# Schematic.net
KiCad netlist of a schematic drawn in EAGLE
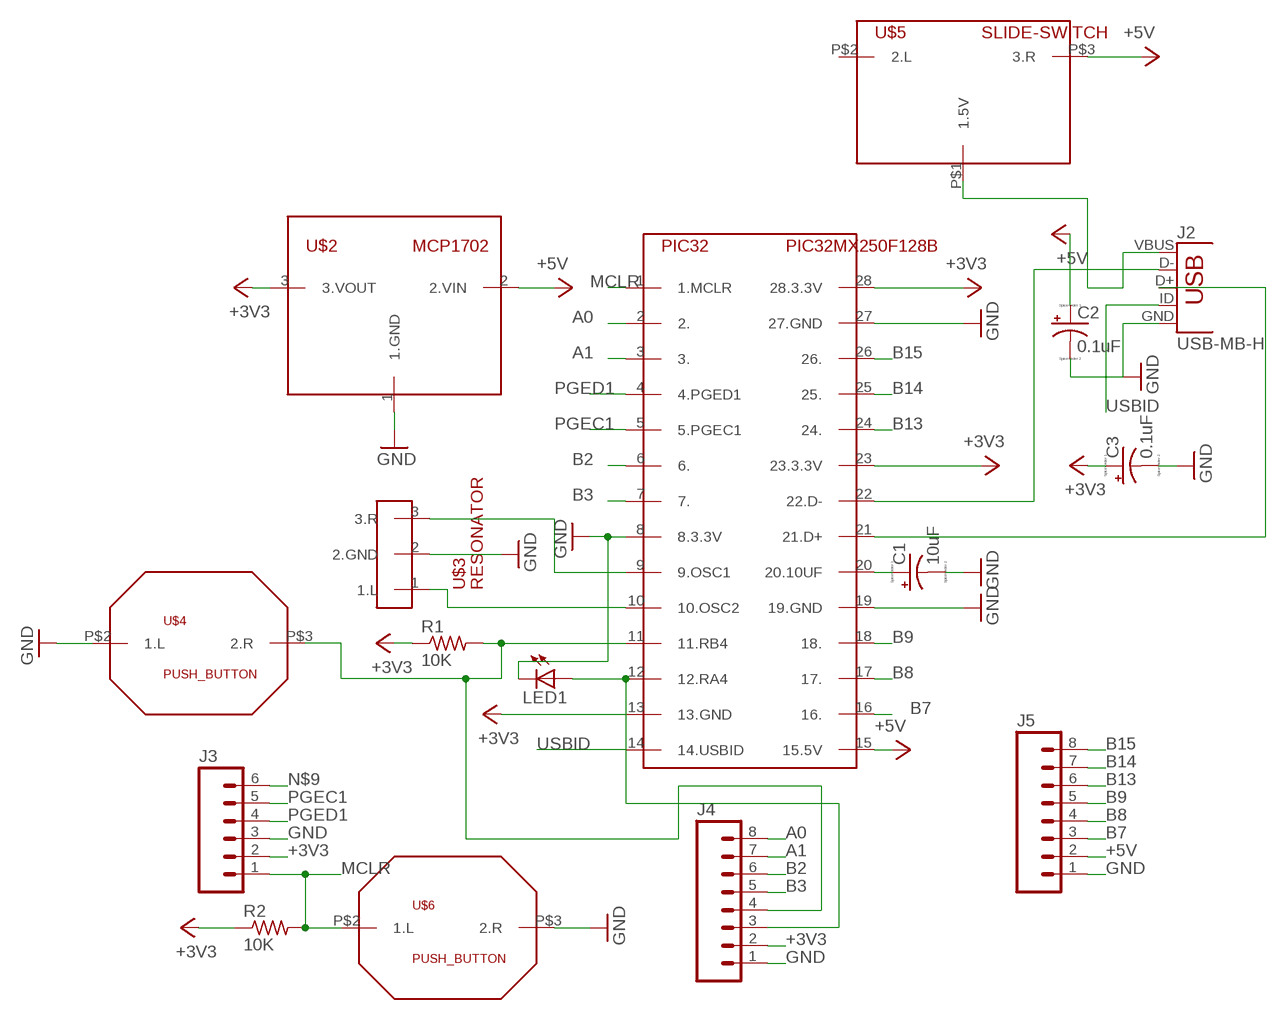
[diagram p0: schematic, sheet 1]

(export (version "E")
  (design (tool "Eeschema 10.0.6"))
  (components
    (comp (ref "C1")
      (value "10uF")
      (footprint "eagle-import:E2,5-5")
      (libsource (lib "eagle-import") (part "CPOL-USE2.5-5"))
    )
    (comp (ref "C2")
      (value "0.1uF")
      (footprint "eagle-import:E2,5-5")
      (libsource (lib "eagle-import") (part "CPOL-USE2.5-5"))
    )
    (comp (ref "C3")
      (value "0.1uF")
      (footprint "eagle-import:E2,5-5")
      (libsource (lib "eagle-import") (part "CPOL-USE2.5-5"))
    )
    (comp (ref "J2")
      (value "USB-MB-H")
      (footprint "eagle-import:USB-MB-H")
      (libsource (lib "eagle-import") (part "USB-MB-H"))
    )
    (comp (ref "J3")
      (value "M06SILK_FEMALE_PTH")
      (footprint "eagle-import:1X06")
      (libsource (lib "eagle-import") (part "M06SILK_FEMALE_PTH"))
    )
    (comp (ref "J4")
      (value "M08SILK_FEMALE_PTH")
      (footprint "eagle-import:1X08")
      (libsource (lib "eagle-import") (part "M08SILK_FEMALE_PTH"))
    )
    (comp (ref "J5")
      (value "M08SILK_FEMALE_PTH")
      (footprint "eagle-import:1X08")
      (libsource (lib "eagle-import") (part "M08SILK_FEMALE_PTH"))
    )
    (comp (ref "LED1")
      (value "LED3MM")
      (footprint "eagle-import:LED3MM")
      (libsource (lib "eagle-import") (part "LED3MM"))
    )
    (comp (ref "PIC32")
      (value "PIC32MX250F128B")
      (footprint "eagle-import:DIL28-3")
      (libsource (lib "eagle-import") (part "PIC32MX250F128B"))
    )
    (comp (ref "R1")
      (value "10K")
      (footprint "eagle-import:0207_10")
      (libsource (lib "eagle-import") (part "R-US_0207/10"))
    )
    (comp (ref "R2")
      (value "10K")
      (footprint "eagle-import:0207_10")
      (libsource (lib "eagle-import") (part "R-US_0207/10"))
    )
    (comp (ref "U$2")
      (value "MCP1702")
      (footprint "eagle-import:TO92")
      (libsource (lib "eagle-import") (part "MCP1702"))
    )
    (comp (ref "U$3")
      (value "RESONATOR")
      (footprint "eagle-import:1X03")
      (libsource (lib "eagle-import") (part "RESONATOR"))
    )
    (comp (ref "U$4")
      (value "PUSH_BUTTON")
      (footprint "eagle-import:PUSH_BUTTON")
      (libsource (lib "eagle-import") (part "PUSH_BUTTON"))
    )
    (comp (ref "U$5")
      (value "SLIDE-SWITCH")
      (footprint "eagle-import:SLIDE-SWITCH")
      (libsource (lib "eagle-import") (part "SLIDE-SWITCH"))
    )
    (comp (ref "U$6")
      (value "PUSH_BUTTON")
      (footprint "eagle-import:PUSH_BUTTON")
      (libsource (lib "eagle-import") (part "PUSH_BUTTON"))
    )
  )
  (nets
    (net (code "1") (name "+3V3") (class "Default")
      (node (ref "C3") (pin "+") (pinfunction "+_+") (pintype "passive"))
      (node (ref "J3") (pin "2") (pinfunction "2_2") (pintype "passive"))
      (node (ref "J4") (pin "2") (pinfunction "2_2") (pintype "passive"))
      (node (ref "PIC32") (pin "13") (pinfunction "13.GND_13") (pintype "bidirectional"))
      (node (ref "PIC32") (pin "23") (pinfunction "23.3.3V_23") (pintype "bidirectional"))
      (node (ref "PIC32") (pin "28") (pinfunction "28.3.3V_28") (pintype "bidirectional"))
      (node (ref "R1") (pin "1") (pinfunction "1_1") (pintype "passive"))
      (node (ref "R2") (pin "1") (pinfunction "1_1") (pintype "passive"))
      (node (ref "U$2") (pin "3") (pinfunction "3.VOUT_3") (pintype "bidirectional"))
    )
    (net (code "2") (name "+5V") (class "Default")
      (node (ref "C2") (pin "+") (pinfunction "+_+") (pintype "passive"))
      (node (ref "J5") (pin "2") (pinfunction "2_2") (pintype "passive"))
      (node (ref "PIC32") (pin "15") (pinfunction "15.5V_15") (pintype "bidirectional"))
      (node (ref "U$2") (pin "2") (pinfunction "2.VIN_2") (pintype "bidirectional"))
      (node (ref "U$5") (pin "P$3") (pinfunction "3.R_P$3") (pintype "bidirectional"))
    )
    (net (code "3") (name "/A0") (class "Default")
      (node (ref "J4") (pin "8") (pinfunction "8_8") (pintype "passive"))
      (node (ref "PIC32") (pin "2") (pinfunction "2._2") (pintype "bidirectional"))
    )
    (net (code "4") (name "/A1") (class "Default")
      (node (ref "J4") (pin "7") (pinfunction "7_7") (pintype "passive"))
      (node (ref "PIC32") (pin "3") (pinfunction "3._3") (pintype "bidirectional"))
    )
    (net (code "5") (name "/B2") (class "Default")
      (node (ref "J4") (pin "6") (pinfunction "6_6") (pintype "passive"))
      (node (ref "PIC32") (pin "6") (pinfunction "6._6") (pintype "bidirectional"))
    )
    (net (code "6") (name "/B3") (class "Default")
      (node (ref "J4") (pin "5") (pinfunction "5_5") (pintype "passive"))
      (node (ref "PIC32") (pin "7") (pinfunction "7._7") (pintype "bidirectional"))
    )
    (net (code "7") (name "/B7") (class "Default")
      (node (ref "J5") (pin "3") (pinfunction "3_3") (pintype "passive"))
      (node (ref "PIC32") (pin "16") (pinfunction "16._16") (pintype "bidirectional"))
    )
    (net (code "8") (name "/B8") (class "Default")
      (node (ref "J5") (pin "4") (pinfunction "4_4") (pintype "passive"))
      (node (ref "PIC32") (pin "17") (pinfunction "17._17") (pintype "bidirectional"))
    )
    (net (code "9") (name "/B9") (class "Default")
      (node (ref "J5") (pin "5") (pinfunction "5_5") (pintype "passive"))
      (node (ref "PIC32") (pin "18") (pinfunction "18._18") (pintype "bidirectional"))
    )
    (net (code "10") (name "/B13") (class "Default")
      (node (ref "J5") (pin "6") (pinfunction "6_6") (pintype "passive"))
      (node (ref "PIC32") (pin "24") (pinfunction "24._24") (pintype "bidirectional"))
    )
    (net (code "11") (name "/B14") (class "Default")
      (node (ref "J5") (pin "7") (pinfunction "7_7") (pintype "passive"))
      (node (ref "PIC32") (pin "25") (pinfunction "25._25") (pintype "bidirectional"))
    )
    (net (code "12") (name "/B15") (class "Default")
      (node (ref "J5") (pin "8") (pinfunction "8_8") (pintype "passive"))
      (node (ref "PIC32") (pin "26") (pinfunction "26._26") (pintype "bidirectional"))
    )
    (net (code "13") (name "/MCLR") (class "Default")
      (node (ref "J3") (pin "1") (pinfunction "1_1") (pintype "passive"))
      (node (ref "PIC32") (pin "1") (pinfunction "1.MCLR_1") (pintype "bidirectional"))
      (node (ref "R2") (pin "2") (pinfunction "2_2") (pintype "passive"))
      (node (ref "U$6") (pin "P$2") (pinfunction "1.L_P$2") (pintype "bidirectional"))
    )
    (net (code "14") (name "/N$9") (class "Default")
      (node (ref "J3") (pin "6") (pinfunction "6_6") (pintype "passive"))
    )
    (net (code "15") (name "/PGEC1") (class "Default")
      (node (ref "J3") (pin "5") (pinfunction "5_5") (pintype "passive"))
      (node (ref "PIC32") (pin "5") (pinfunction "5.PGEC1_5") (pintype "bidirectional"))
    )
    (net (code "16") (name "/PGED1") (class "Default")
      (node (ref "J3") (pin "4") (pinfunction "4_4") (pintype "passive"))
      (node (ref "PIC32") (pin "4") (pinfunction "4.PGED1_4") (pintype "bidirectional"))
    )
    (net (code "17") (name "/USBID") (class "Default")
      (node (ref "J2") (pin "ID") (pinfunction "2.ID_ID") (pintype "bidirectional"))
      (node (ref "PIC32") (pin "14") (pinfunction "14.USBID_14") (pintype "bidirectional"))
    )
    (net (code "18") (name "GND") (class "Default")
      (node (ref "C1") (pin "-") (pinfunction "-_-") (pintype "passive"))
      (node (ref "C2") (pin "-") (pinfunction "-_-") (pintype "passive"))
      (node (ref "C3") (pin "-") (pinfunction "-_-") (pintype "passive"))
      (node (ref "J2") (pin "GND") (pinfunction "1.GND_GND") (pintype "bidirectional"))
      (node (ref "J3") (pin "3") (pinfunction "3_3") (pintype "passive"))
      (node (ref "J4") (pin "1") (pinfunction "1_1") (pintype "passive"))
      (node (ref "J5") (pin "1") (pinfunction "1_1") (pintype "passive"))
      (node (ref "LED1") (pin "K") (pinfunction "C_K") (pintype "passive"))
      (node (ref "PIC32") (pin "19") (pinfunction "19.GND_19") (pintype "bidirectional"))
      (node (ref "PIC32") (pin "27") (pinfunction "27.GND_27") (pintype "bidirectional"))
      (node (ref "PIC32") (pin "8") (pinfunction "8.3.3V_8") (pintype "bidirectional"))
      (node (ref "U$2") (pin "1") (pinfunction "1.GND_1") (pintype "bidirectional"))
      (node (ref "U$3") (pin "2") (pinfunction "2.GND_2") (pintype "bidirectional"))
      (node (ref "U$4") (pin "P$2") (pinfunction "1.L_P$2") (pintype "bidirectional"))
      (node (ref "U$6") (pin "P$3") (pinfunction "2.R_P$3") (pintype "bidirectional"))
    )
    (net (code "19") (name "Net-(J2-3.D+)") (class "Default")
      (node (ref "J2") (pin "D+") (pinfunction "3.D+_D+") (pintype "bidirectional"))
      (node (ref "PIC32") (pin "21") (pinfunction "21.D+_21") (pintype "bidirectional"))
    )
    (net (code "20") (name "Net-(J2-4.D-)") (class "Default")
      (node (ref "J2") (pin "D-") (pinfunction "4.D-_D-") (pintype "bidirectional"))
      (node (ref "PIC32") (pin "22") (pinfunction "22.D-_22") (pintype "bidirectional"))
    )
    (net (code "21") (name "Net-(J2-5.VBUS)") (class "Default")
      (node (ref "J2") (pin "VBUS") (pinfunction "5.VBUS_VBUS") (pintype "bidirectional"))
      (node (ref "U$5") (pin "P$1") (pinfunction "1.5V_P$1") (pintype "bidirectional"))
    )
    (net (code "22") (name "Net-(PIC32-9.OSC1)") (class "Default")
      (node (ref "PIC32") (pin "9") (pinfunction "9.OSC1_9") (pintype "bidirectional"))
      (node (ref "U$3") (pin "3") (pinfunction "3.R_3") (pintype "bidirectional"))
    )
    (net (code "23") (name "Net-(PIC32-10.OSC2)") (class "Default")
      (node (ref "PIC32") (pin "10") (pinfunction "10.OSC2_10") (pintype "bidirectional"))
      (node (ref "U$3") (pin "1") (pinfunction "1.L_1") (pintype "bidirectional"))
    )
    (net (code "24") (name "Net-(PIC32-11.RB4)") (class "Default")
      (node (ref "J4") (pin "4") (pinfunction "4_4") (pintype "passive"))
      (node (ref "PIC32") (pin "11") (pinfunction "11.RB4_11") (pintype "bidirectional"))
      (node (ref "R1") (pin "2") (pinfunction "2_2") (pintype "passive"))
      (node (ref "U$4") (pin "P$3") (pinfunction "2.R_P$3") (pintype "bidirectional"))
    )
    (net (code "25") (name "Net-(PIC32-12.RA4)") (class "Default")
      (node (ref "J4") (pin "3") (pinfunction "3_3") (pintype "passive"))
      (node (ref "LED1") (pin "A") (pinfunction "A_A") (pintype "passive"))
      (node (ref "PIC32") (pin "12") (pinfunction "12.RA4_12") (pintype "bidirectional"))
    )
    (net (code "26") (name "Net-(PIC32-20.10UF)") (class "Default")
      (node (ref "C1") (pin "+") (pinfunction "+_+") (pintype "passive"))
      (node (ref "PIC32") (pin "20") (pinfunction "20.10UF_20") (pintype "bidirectional"))
    )
    (net (code "27") (name "unconnected-(U$5-2.L-PadP$2)") (class "Default")
      (node (ref "U$5") (pin "P$2") (pinfunction "2.L_P$2") (pintype "bidirectional"))
    )
  )
)
